# LDO.net
KiCad netlist of a schematic drawn in Altium Designer
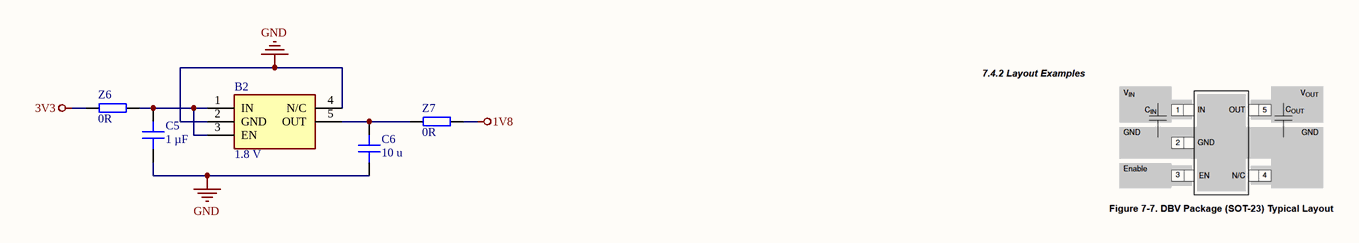
[diagram p0: LDO.SchDoc]

(export (version "E")
  (design (tool "Eeschema 10.0.6"))
  (components
    (comp (ref "B2")
      (value "1.8 V")
      (footprint "SOT23-5_L")
      (description "300mA, ultra-low noise, LDO, 1V6 < Vin < 6V, 0.8V < Vout < 5V5")
      (fields
        (field (name "MOUSER PART NUMBER") "595-TPS7A2018PDBVR")
        (field (name "MANUFACTURER_PART_NUMBER") "TPS7A2018PDBVR")
        (field (name "CREATED FROM") "RWeimer")
      )
      (libsource (lib "user") (part "TPS7A2018PDBVR"))
    )
    (comp (ref "C5")
      (value "1 µF")
      (footprint "C_0603")
      (description "Capacitor 0603, 25 VDC, 1 µF, X7R")
      (fields
        (field (name "MANUFACTURER PART NUMBER") "C0603C105K3RAC7411")
        (field (name "MANUFACTURER") "KEMET")
        (field (name "CREATED FROM") "MGremer")
      )
      (libsource (lib "user") (part "Capacitor"))
    )
    (comp (ref "C6")
      (value "10 u")
      (footprint "C_0603_TE")
      (description "10uF 35V X5R ±10% 0603 Multilayer Ceramic Capacitors MLCC")
      (fields
        (field (name "MANUFACTURER PART NUMBER") "HGC0603R5106K350NTHJ")
        (field (name "MANUFACTURER") "Chinocera")
        (field (name "CREATED FROM") "RWeimer")
      )
      (libsource (lib "user") (part "Capacitor"))
    )
    (comp (ref "Z6")
      (value "0R")
      (footprint "RES 0603_1608")
      (description "SMD resistor E24 series")
      (fields
        (field (name "MANUFACTURER PART NUMBER") "RC0603JR-070RL")
        (field (name "MANUFACTURER") "YAGEO")
        (field (name "CREATED FROM") "MGremer")
      )
      (libsource (lib "user") (part "Resistor"))
    )
    (comp (ref "Z7")
      (value "0R")
      (footprint "RES 0603_1608")
      (description "SMD resistor E24 series")
      (fields
        (field (name "MANUFACTURER PART NUMBER") "RC0603JR-070RL")
        (field (name "MANUFACTURER") "YAGEO")
        (field (name "CREATED FROM") "MGremer")
      )
      (libsource (lib "user") (part "Resistor"))
    )
  )
  (nets
    (net (code "1") (name "1V8") (class "Default")
      (node (ref "Z7") (pin "1") (pinfunction "1_1") (pintype "passive"))
    )
    (net (code "2") (name "3V3") (class "Default")
      (node (ref "Z6") (pin "2") (pinfunction "2_2") (pintype "passive"))
    )
    (net (code "3") (name "GND") (class "Default")
      (node (ref "B2") (pin "2") (pinfunction "GND_2") (pintype "passive"))
      (node (ref "B2") (pin "4") (pinfunction "N/C_4") (pintype "passive"))
      (node (ref "C5") (pin "1") (pinfunction "1_1") (pintype "passive"))
      (node (ref "C6") (pin "2") (pinfunction "2_2") (pintype "passive"))
    )
    (net (code "4") (name "Net-(B2-EN)") (class "Default")
      (node (ref "B2") (pin "1") (pinfunction "IN_1") (pintype "passive"))
      (node (ref "B2") (pin "3") (pinfunction "EN_3") (pintype "passive"))
      (node (ref "C5") (pin "2") (pinfunction "2_2") (pintype "passive"))
      (node (ref "Z6") (pin "1") (pinfunction "1_1") (pintype "passive"))
    )
    (net (code "5") (name "Net-(B2-OUT)") (class "Default")
      (node (ref "B2") (pin "5") (pinfunction "OUT_5") (pintype "passive"))
      (node (ref "C6") (pin "1") (pinfunction "1_1") (pintype "passive"))
      (node (ref "Z7") (pin "2") (pinfunction "2_2") (pintype "passive"))
    )
  )
)
